# Sheet1.net
KiCad netlist of a schematic drawn in Altium Designer
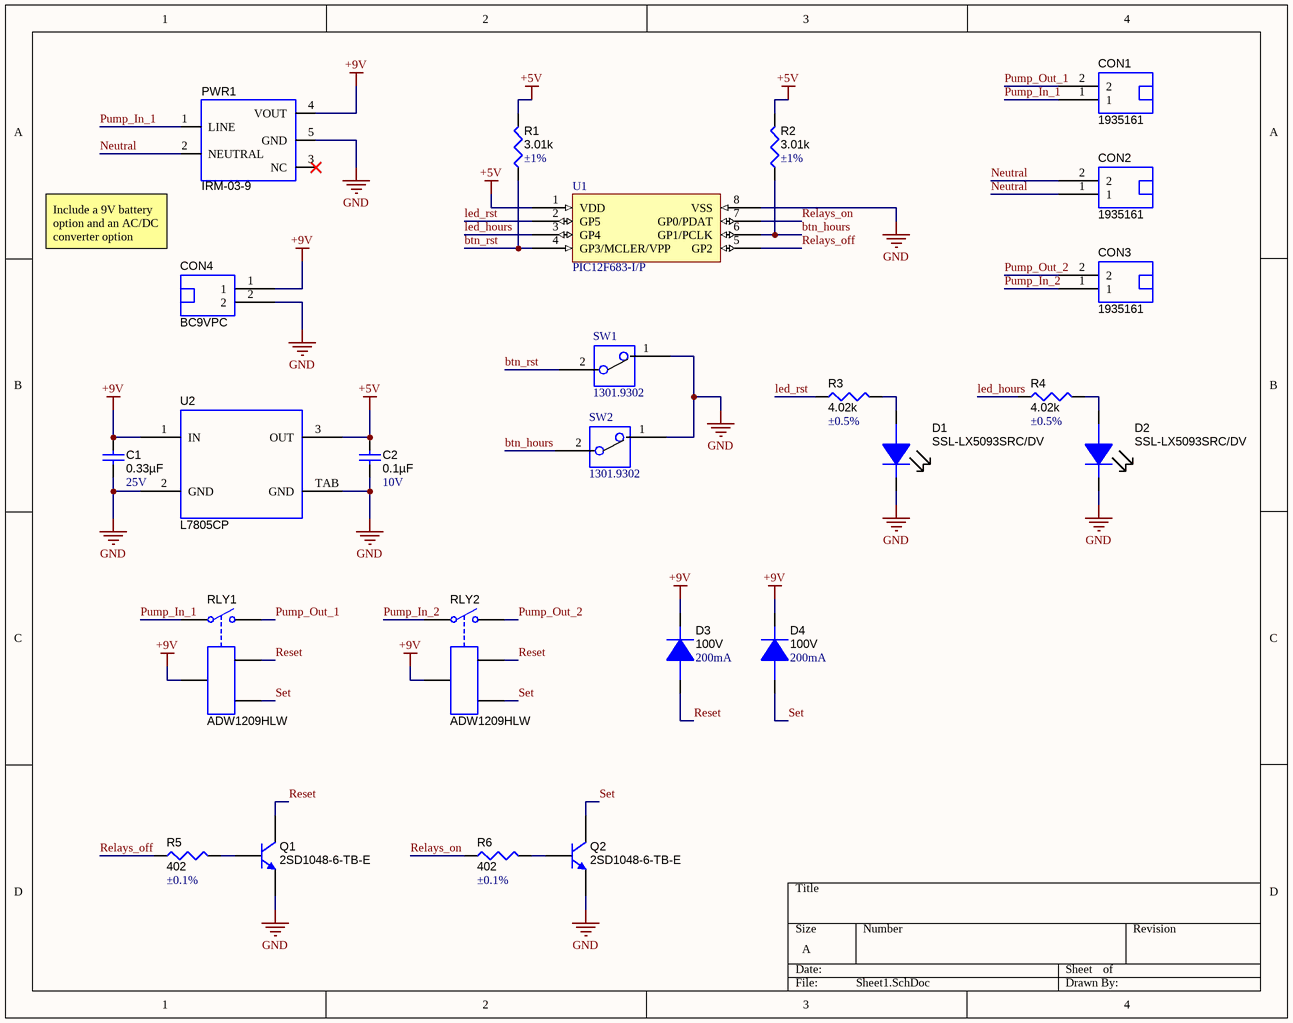
[diagram p0: Sheet1.SchDoc]

(export (version "E")
  (design (tool "Eeschema 10.0.6"))
  (components
    (comp (ref "C1")
      (value "0.33µF")
      (footprint "0805")
      (description "CAP CER 0.33UF 25V 10% X7R 0805")
      (fields
        (field (name "MANUFACTURER PART NUMBER") "08053C334KAZ2A")
        (field (name "MANUFACTURER") "AVX Corporation")
        (field (name "PARAMETERS") "25V")
      )
      (libsource (lib "Lynntech Instrumentation") (part "Capacitor{colon} Ceramic"))
    )
    (comp (ref "C2")
      (value "0.1µF")
      (footprint "0402_C")
      (description "CAP CER 0.1UF 10V 10% X7R 0402")
      (fields
        (field (name "MANUFACTURER PART NUMBER") "C1005X7R1A104K")
        (field (name "MANUFACTURER") "TDK Corporation")
        (field (name "PARAMETERS") "10V")
      )
      (libsource (lib "Lynntech Instrumentation") (part "Capacitor{colon} Ceramic"))
    )
    (comp (ref "CON1")
      (value "1935161")
      (footprint "5MM-CON-2")
      (fields (field (name "MANUFACTURER") "Phoenix Contact"))
      (libsource (lib "Lynntech Instrumentation") (part "JST{colon} B2B-PH-K-S(LF)(SN)"))
    )
    (comp (ref "CON2")
      (value "1935161")
      (footprint "5MM-CON-2")
      (fields (field (name "MANUFACTURER") "Phoenix Contact"))
      (libsource (lib "Lynntech Instrumentation") (part "JST{colon} B2B-PH-K-S(LF)(SN)"))
    )
    (comp (ref "CON3")
      (value "1935161")
      (footprint "5MM-CON-2")
      (fields (field (name "MANUFACTURER") "Phoenix Contact"))
      (libsource (lib "Lynntech Instrumentation") (part "JST{colon} B2B-PH-K-S(LF)(SN)"))
    )
    (comp (ref "CON4")
      (value "BC9VPC")
      (footprint "9V BATTERY HOLDER")
      (description "BATTERY HOLDER (OPEN) 9V 1 CELL PC PIN")
      (fields (field (name "MANUFACTURER") "MPD"))
      (libsource (lib "Lynntech Instrumentation") (part "JST{colon} B2B-PH-K-S(LF)(SN)"))
    )
    (comp (ref "D1")
      (value "SSL-LX5093SRC/DV")
      (footprint "RB-.1/.250")
      (description "LED 5MM 1500MCD SUPER RED WTRCLR")
      (fields (field (name "MANUFACTURER") "Lumex Opto/Components Inc"))
      (libsource (lib "Lynntech Instrumentation") (part "LED"))
    )
    (comp (ref "D2")
      (value "SSL-LX5093SRC/DV")
      (footprint "RB-.1/.250")
      (description "LED 5MM 1500MCD SUPER RED WTRCLR")
      (fields (field (name "MANUFACTURER") "Lumex Opto/Components Inc"))
      (libsource (lib "Lynntech Instrumentation") (part "LED"))
    )
    (comp (ref "D3")
      (value "100V")
      (footprint "SOD123")
      (description "DIODE GEN PURP 100V 200MA SOD123")
      (fields
        (field (name "MANUFACTURER PART NUMBER") "MMSD914T1G")
        (field (name "MANUFACTURER") "ON Semiconductor")
        (field (name "PARAMETERS") "200mA")
      )
      (libsource (lib "Lynntech Instrumentation") (part "DIODE"))
    )
    (comp (ref "D4")
      (value "100V")
      (footprint "SOD123")
      (description "DIODE GEN PURP 100V 200MA SOD123")
      (fields
        (field (name "MANUFACTURER PART NUMBER") "MMSD914T1G")
        (field (name "MANUFACTURER") "ON Semiconductor")
        (field (name "PARAMETERS") "200mA")
      )
      (libsource (lib "Lynntech Instrumentation") (part "DIODE"))
    )
    (comp (ref "PWR1")
      (value "IRM-03-9")
      (footprint "IRM-03-9")
      (description "ENCLOSED AC DC CONVERTERS 1 UITGANG 9V    333MA 85 ~ 305 VAC, 120 ~ 430 VDC INPUT")
      (fields (field (name "MANUFACTURER") "Mean Well"))
      (libsource (lib "Lynntech Instrumentation") (part "IRM-03-9"))
    )
    (comp (ref "Q1")
      (value "2SD1048-6-TB-E")
      (footprint "SOT-23")
      (description "BIPOLAR (BJT) TRANSISTOR NPN 15V 700MA 250MHZ 200MW SURFACE MOUNT 3-CP")
      (fields (field (name "MANUFACTURER") "ON Semiconductor"))
      (libsource (lib "Lynntech Instrumentation") (part "2N3904"))
    )
    (comp (ref "Q2")
      (value "2SD1048-6-TB-E")
      (footprint "SOT-23")
      (description "BIPOLAR (BJT) TRANSISTOR NPN 15V 700MA 250MHZ 200MW SURFACE MOUNT 3-CP")
      (fields (field (name "MANUFACTURER") "ON Semiconductor"))
      (libsource (lib "Lynntech Instrumentation") (part "2N3904"))
    )
    (comp (ref "R1")
      (value "3.01k")
      (footprint "0603_R")
      (description "RES SMD 3.01K OHM 1% 1/10W 0402")
      (fields
        (field (name "MANUFACTURER PART NUMBER") "ERJ-2RKF3011X")
        (field (name "MANUFACTURER") "Panasonic Electronic Components")
        (field (name "PARAMETERS") "±1%")
      )
      (libsource (lib "Lynntech Instrumentation") (part "Resistor"))
    )
    (comp (ref "R2")
      (value "3.01k")
      (footprint "0603_R")
      (description "RES SMD 3.01K OHM 1% 1/10W 0402")
      (fields
        (field (name "MANUFACTURER PART NUMBER") "ERJ-2RKF3011X")
        (field (name "MANUFACTURER") "Panasonic Electronic Components")
        (field (name "PARAMETERS") "±1%")
      )
      (libsource (lib "Lynntech Instrumentation") (part "Resistor"))
    )
    (comp (ref "R3")
      (value "4.02k")
      (footprint "0805_R")
      (description "RES 4.02K OHM 1/10W .5% 0805 SMD")
      (fields
        (field (name "MANUFACTURER PART NUMBER") "RR1220P-4021-D-M")
        (field (name "MANUFACTURER") "Susumu")
        (field (name "PARAMETERS") "±0.5%")
      )
      (libsource (lib "Lynntech Instrumentation") (part "Resistor"))
    )
    (comp (ref "R4")
      (value "4.02k")
      (footprint "0805_R")
      (description "RES 4.02K OHM 1/10W .5% 0805 SMD")
      (fields
        (field (name "MANUFACTURER PART NUMBER") "RR1220P-4021-D-M")
        (field (name "MANUFACTURER") "Susumu")
        (field (name "PARAMETERS") "±0.5%")
      )
      (libsource (lib "Lynntech Instrumentation") (part "Resistor"))
    )
    (comp (ref "R5")
      (value "402")
      (footprint "0805_R")
      (description "RES 402 OHM 1/10W .1% 0805 SMD")
      (fields
        (field (name "MANUFACTURER PART NUMBER") "RR1220P-4020-B-M-T5")
        (field (name "MANUFACTURER") "Susumu")
        (field (name "PARAMETERS") "±0.1%")
      )
      (libsource (lib "Lynntech Instrumentation") (part "Resistor"))
    )
    (comp (ref "R6")
      (value "402")
      (footprint "0805_R")
      (description "RES 402 OHM 1/10W .1% 0805 SMD")
      (fields
        (field (name "MANUFACTURER PART NUMBER") "RR1220P-4020-B-M-T5")
        (field (name "MANUFACTURER") "Susumu")
        (field (name "PARAMETERS") "±0.1%")
      )
      (libsource (lib "Lynntech Instrumentation") (part "Resistor"))
    )
    (comp (ref "RLY1")
      (value "ADW1209HLW")
      (footprint "ADW1 LOW-PROFILE RELAY")
      (description "GENERAL PURPOSE TWO-COIL RELAY SPST-NO (1 FORM A) 9VDC COIL THROUGH HOLE")
      (fields (field (name "MANUFACTURER") "Panasonic - ECG"))
      (libsource (lib "Lynntech Instrumentation") (part "RELAY{colon} SPST_TWO-COIL"))
    )
    (comp (ref "RLY2")
      (value "ADW1209HLW")
      (footprint "ADW1 LOW-PROFILE RELAY")
      (description "GENERAL PURPOSE TWO-COIL RELAY SPST-NO (1 FORM A) 9VDC COIL THROUGH HOLE")
      (fields (field (name "MANUFACTURER") "Panasonic - ECG"))
      (libsource (lib "Lynntech Instrumentation") (part "RELAY{colon} SPST_TWO-COIL"))
    )
    (comp (ref "SW1")
      (value "1301.9302")
      (footprint "4 PIN SPST PUSH BUTTON")
      (description "TACTILE SWITCH SPST-NO TOP ACTUATED THROUGH HOLE")
      (fields (field (name "MANUFACTURER") "Schurter Inc."))
      (libsource (lib "Lynntech Instrumentation") (part "Switch_SPST"))
    )
    (comp (ref "SW2")
      (value "1301.9302")
      (footprint "4 PIN SPST PUSH BUTTON")
      (description "TACTILE SWITCH SPST-NO TOP ACTUATED THROUGH HOLE")
      (fields (field (name "MANUFACTURER") "Schurter Inc."))
      (libsource (lib "Lynntech Instrumentation") (part "Switch_SPST"))
    )
    (comp (ref "U1")
      (value "PIC12F683-I/P")
      (footprint "DIP8")
      (description "IC MCU 8BIT 3.5KB FLASH 8DIP")
      (fields (field (name "MANUFACTURER") "Microchip Technology"))
      (libsource (lib "Lynntech Instrumentation") (part "PIC12F675"))
    )
    (comp (ref "U2")
      (value "L7805CP")
      (footprint "L7805")
      (description "IC REG LDO 5V 1.5A TO220FP")
      (fields (field (name "MANUFACTURER") "STMicroelectronics"))
      (libsource (lib "Lynntech Instrumentation") (part "L7805"))
    )
  )
  (nets
    (net (code "1") (name "+5V") (class "Default")
      (node (ref "C2") (pin "2") (pinfunction "2_2") (pintype "passive"))
      (node (ref "R1") (pin "2") (pinfunction "2_2") (pintype "passive"))
      (node (ref "R2") (pin "2") (pinfunction "2_2") (pintype "passive"))
      (node (ref "U1") (pin "1") (pinfunction "VDD_1") (pintype "input"))
      (node (ref "U2") (pin "3") (pinfunction "OUT_3") (pintype "passive"))
    )
    (net (code "2") (name "+9V") (class "Default")
      (node (ref "C1") (pin "2") (pinfunction "2_2") (pintype "passive"))
      (node (ref "CON4") (pin "1") (pinfunction "1_1") (pintype "passive"))
      (node (ref "D3") (pin "2") (pinfunction "K_2") (pintype "passive"))
      (node (ref "D4") (pin "2") (pinfunction "K_2") (pintype "passive"))
      (node (ref "PWR1") (pin "4") (pinfunction "VOUT_4") (pintype "passive"))
      (node (ref "RLY1") (pin "2") (pinfunction "2_2") (pintype "passive"))
      (node (ref "RLY2") (pin "2") (pinfunction "2_2") (pintype "passive"))
      (node (ref "U2") (pin "1") (pinfunction "IN_1") (pintype "passive"))
    )
    (net (code "3") (name "/Neutral") (class "Default")
      (node (ref "CON2") (pin "1") (pinfunction "1_1") (pintype "passive"))
      (node (ref "CON2") (pin "2") (pinfunction "2_2") (pintype "passive"))
      (node (ref "PWR1") (pin "2") (pinfunction "NEUTRAL_2") (pintype "passive"))
    )
    (net (code "4") (name "/Pump_In_1") (class "Default")
      (node (ref "CON1") (pin "1") (pinfunction "1_1") (pintype "passive"))
      (node (ref "PWR1") (pin "1") (pinfunction "LINE_1") (pintype "passive"))
      (node (ref "RLY1") (pin "5") (pinfunction "5_5") (pintype "passive"))
    )
    (net (code "5") (name "/Pump_In_2") (class "Default")
      (node (ref "CON3") (pin "1") (pinfunction "1_1") (pintype "passive"))
      (node (ref "RLY2") (pin "5") (pinfunction "5_5") (pintype "passive"))
    )
    (net (code "6") (name "/Pump_Out_1") (class "Default")
      (node (ref "CON1") (pin "2") (pinfunction "2_2") (pintype "passive"))
      (node (ref "RLY1") (pin "4") (pinfunction "4_4") (pintype "passive"))
    )
    (net (code "7") (name "/Pump_Out_2") (class "Default")
      (node (ref "CON3") (pin "2") (pinfunction "2_2") (pintype "passive"))
      (node (ref "RLY2") (pin "4") (pinfunction "4_4") (pintype "passive"))
    )
    (net (code "8") (name "/Relays_off") (class "Default")
      (node (ref "R5") (pin "1") (pinfunction "1_1") (pintype "passive"))
      (node (ref "U1") (pin "5") (pinfunction "GP2_5") (pintype "bidirectional"))
    )
    (net (code "9") (name "/Relays_on") (class "Default")
      (node (ref "R6") (pin "1") (pinfunction "1_1") (pintype "passive"))
      (node (ref "U1") (pin "7") (pinfunction "GP0/PDAT_7") (pintype "bidirectional"))
    )
    (net (code "10") (name "/Reset") (class "Default")
      (node (ref "D3") (pin "1") (pinfunction "A_1") (pintype "passive"))
      (node (ref "Q1") (pin "C") (pinfunction "C_C") (pintype "passive"))
      (node (ref "RLY1") (pin "3") (pinfunction "3_3") (pintype "passive"))
      (node (ref "RLY2") (pin "3") (pinfunction "3_3") (pintype "passive"))
    )
    (net (code "11") (name "/Set") (class "Default")
      (node (ref "D4") (pin "1") (pinfunction "A_1") (pintype "passive"))
      (node (ref "Q2") (pin "C") (pinfunction "C_C") (pintype "passive"))
      (node (ref "RLY1") (pin "1") (pinfunction "1_1") (pintype "passive"))
      (node (ref "RLY2") (pin "1") (pinfunction "1_1") (pintype "passive"))
    )
    (net (code "12") (name "/btn_hours") (class "Default")
      (node (ref "R2") (pin "1") (pinfunction "1_1") (pintype "passive"))
      (node (ref "SW2") (pin "2") (pintype "passive"))
      (node (ref "U1") (pin "6") (pinfunction "GP1/PCLK_6") (pintype "bidirectional"))
    )
    (net (code "13") (name "/btn_rst") (class "Default")
      (node (ref "R1") (pin "1") (pinfunction "1_1") (pintype "passive"))
      (node (ref "SW1") (pin "2") (pintype "passive"))
      (node (ref "U1") (pin "4") (pinfunction "GP3/MCLER/VPP_4") (pintype "input"))
    )
    (net (code "14") (name "/led_hours") (class "Default")
      (node (ref "R4") (pin "1") (pinfunction "1_1") (pintype "passive"))
      (node (ref "U1") (pin "3") (pinfunction "GP4_3") (pintype "bidirectional"))
    )
    (net (code "15") (name "/led_rst") (class "Default")
      (node (ref "R3") (pin "1") (pinfunction "1_1") (pintype "passive"))
      (node (ref "U1") (pin "2") (pinfunction "GP5_2") (pintype "bidirectional"))
    )
    (net (code "16") (name "GND") (class "Default")
      (node (ref "C1") (pin "1") (pinfunction "1_1") (pintype "passive"))
      (node (ref "C2") (pin "1") (pinfunction "1_1") (pintype "passive"))
      (node (ref "CON4") (pin "2") (pinfunction "2_2") (pintype "passive"))
      (node (ref "D1") (pin "2") (pinfunction "K_2") (pintype "passive"))
      (node (ref "D2") (pin "2") (pinfunction "K_2") (pintype "passive"))
      (node (ref "PWR1") (pin "5") (pinfunction "GND_5") (pintype "passive"))
      (node (ref "Q1") (pin "E") (pinfunction "E_E") (pintype "passive"))
      (node (ref "Q2") (pin "E") (pinfunction "E_E") (pintype "passive"))
      (node (ref "SW1") (pin "1") (pinfunction "1_1") (pintype "passive"))
      (node (ref "SW2") (pin "1") (pinfunction "1_1") (pintype "passive"))
      (node (ref "U1") (pin "8") (pinfunction "VSS_8") (pintype "input"))
      (node (ref "U2") (pin "2") (pinfunction "GND_2") (pintype "passive"))
      (node (ref "U2") (pin "TAB") (pinfunction "GND_TAB") (pintype "passive"))
    )
    (net (code "17") (name "Net-(D1-A)") (class "Default")
      (node (ref "D1") (pin "1") (pinfunction "A_1") (pintype "passive"))
      (node (ref "R3") (pin "2") (pinfunction "2_2") (pintype "passive"))
    )
    (net (code "18") (name "Net-(D2-A)") (class "Default")
      (node (ref "D2") (pin "1") (pinfunction "A_1") (pintype "passive"))
      (node (ref "R4") (pin "2") (pinfunction "2_2") (pintype "passive"))
    )
    (net (code "19") (name "Net-(Q1-PadB)") (class "Default")
      (node (ref "Q1") (pin "B") (pinfunction "B_B") (pintype "passive"))
      (node (ref "R5") (pin "2") (pinfunction "2_2") (pintype "passive"))
    )
    (net (code "20") (name "Net-(Q2-PadB)") (class "Default")
      (node (ref "Q2") (pin "B") (pinfunction "B_B") (pintype "passive"))
      (node (ref "R6") (pin "2") (pinfunction "2_2") (pintype "passive"))
    )
    (net (code "21") (name "unconnected-(PWR1-NC-Pad3)") (class "Default")
      (node (ref "PWR1") (pin "3") (pinfunction "NC_3") (pintype "passive+no_connect"))
    )
  )
)
